# Power.net
KiCad netlist of a schematic drawn in Altium Designer
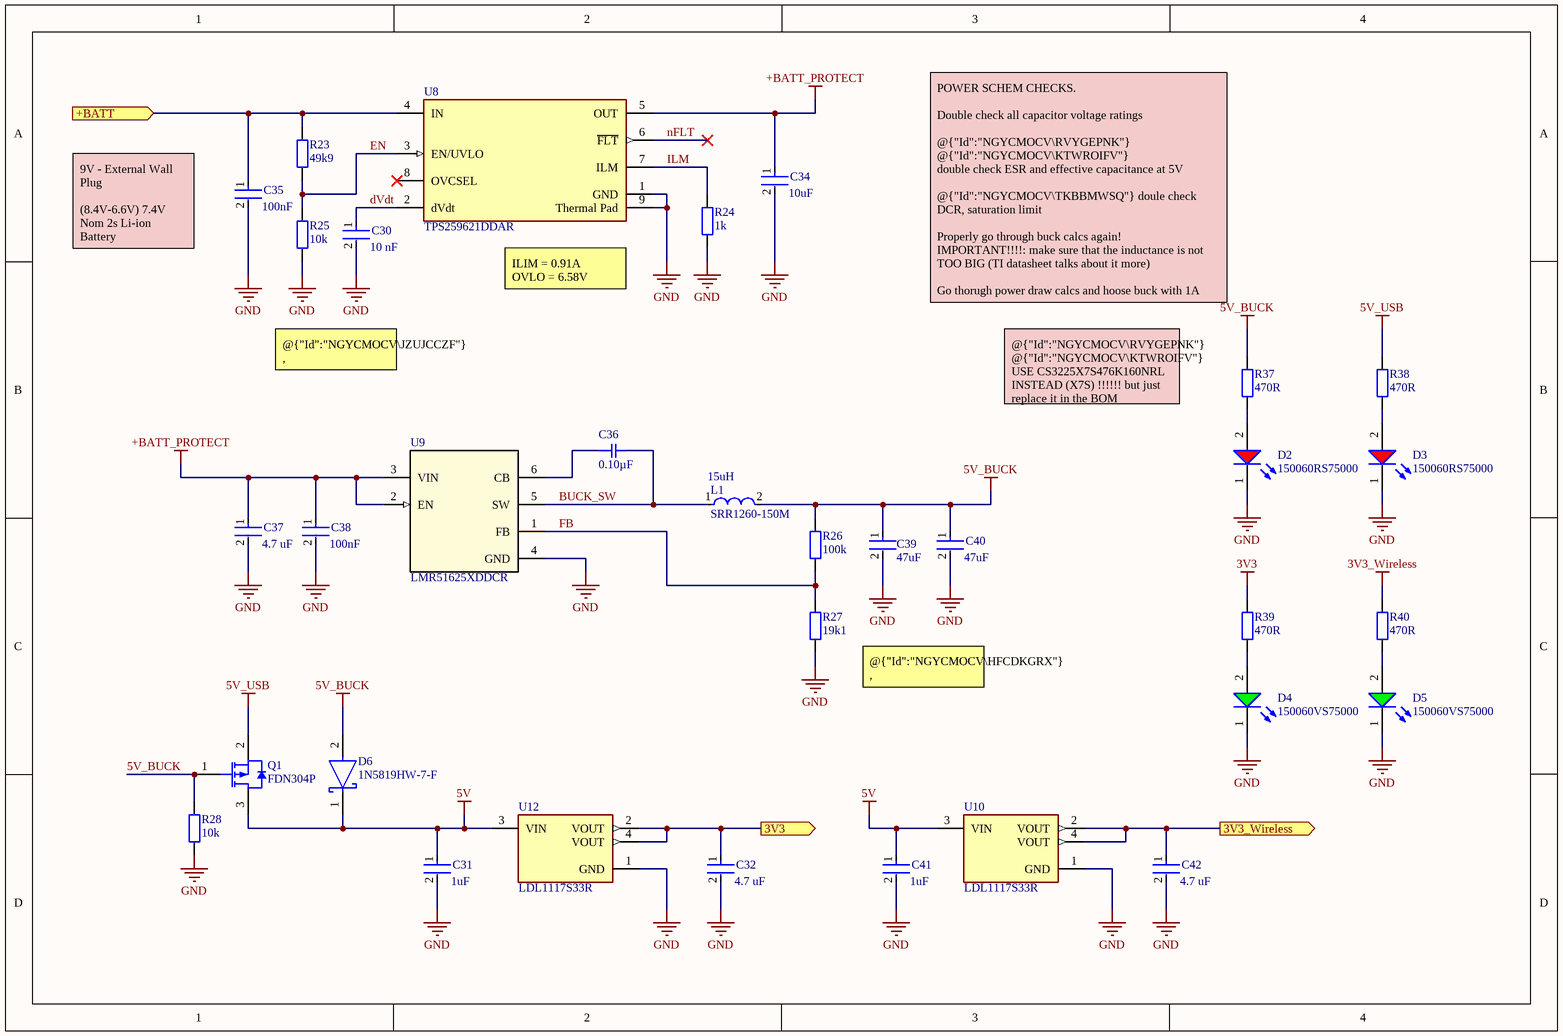
[diagram p0: Power.SchDoc]

(export (version "E")
  (design (tool "Eeschema 10.0.6"))
  (components
    (comp (ref "C30")
      (value "10 nF")
      (footprint "FP-CC0402-MFG")
      (description "CAP CER 10000PF 10V X7R 0402")
      (fields
        (field (name "MANUFACTURER") "YAGEO")
        (field (name "MANUFACTURER PART NUMBER") "CC0402KRX7R6BB103")
      )
      (libsource (lib "Altium Content Vault") (part "11868f565c42a9108669ba33697ecf6"))
    )
    (comp (ref "C31")
      (value "CL21B105KOFNNNE")
      (footprint "FP-CL21-IPC_A")
      (description "CL21 Series 0805 1uF 16V ±10% Tolerance X7R Multilayer Ceramic Chip Capacitor")
      (fields
        (field (name "CAPACITANCE") "1uF")
        (field (name "TOLERANCE") "10%")
        (field (name "VOLTAGE") "16V")
      )
      (libsource (lib "Altium Content Vault") (part "b4654b650e69147ec39a6b967a45e02"))
    )
    (comp (ref "C32")
      (value "4.7 uF")
      (footprint "FP-CC0805-0_85-MFG")
      (description "CAP CER 4.7UF 25V X7R 0805")
      (fields
        (field (name "OCTOPART") "https://octopart.com/cc0805kkx7r8bb475-yageo-51849247")
        (field (name "MANUFACTURER") "Yageo")
      )
      (libsource (lib "Altium Content Vault") (part "11868f565c42a9108669ba33697ecf6"))
    )
    (comp (ref "C34")
      (value "GRM21BC71E106KE11L")
      (footprint "FP-GRM21B-0_2-e0_2_0_7-MFG")
      (description "Chip Multilayer Ceramic Capacitors for General Purpose, 0805, 10uF, X7S, 22%, 10%, 25V")
      (fields
        (field (name "VOLTAGE") "25V")
        (field (name "CAPACITANCE") "10uF")
        (field (name "TOLERANCE") "10%")
      )
      (libsource (lib "Altium Content Vault") (part "b4654b650e69147ec39a6b967a45e02"))
    )
    (comp (ref "C35")
      (value "GRM155R61E104KA87D")
      (footprint "FP-GRM155-0_05-MFG")
      (description "CAP CER 0.1UF 25V X5R 0402")
      (fields
        (field (name "VOLTAGE") "25V")
        (field (name "CAPACITANCE") "100nF")
        (field (name "TOLERANCE") "10%")
      )
      (libsource (lib "Altium Content Vault") (part "11868f565c42a9108669ba33697ecf6"))
    )
    (comp (ref "C36")
      (value "0.10µF")
      (footprint "SMD-0402C")
      (description "CAP CER 0.1UF 10V X5R 0402")
      (fields (field (name "DIGI-KEY PART NUMBER") "490-6297-1-ND") (field (name "VOLTAGE") "10V"))
      (libsource (lib "University of British Columbia") (part "ZRB15XR61A475ME01D"))
    )
    (comp (ref "C37")
      (value "4.7 uF")
      (footprint "FP-CC0805-0_85-MFG")
      (description "CAP CER 4.7UF 25V X7R 0805")
      (fields
        (field (name "OCTOPART") "https://octopart.com/cc0805kkx7r8bb475-yageo-51849247")
        (field (name "MANUFACTURER") "Yageo")
      )
      (libsource (lib "Altium Content Vault") (part "11868f565c42a9108669ba33697ecf6"))
    )
    (comp (ref "C38")
      (value "GRM155R61E104KA87D")
      (footprint "FP-GRM155-0_05-MFG")
      (description "CAP CER 0.1UF 25V X5R 0402")
      (fields
        (field (name "VOLTAGE") "25V")
        (field (name "CAPACITANCE") "100nF")
        (field (name "TOLERANCE") "10%")
      )
      (libsource (lib "Altium Content Vault") (part "11868f565c42a9108669ba33697ecf6"))
    )
    (comp (ref "C39")
      (value "GRM32ER61C476KE15L")
      (footprint "FP-GRM32E-0_3-0_2-IPC_C")
      (description "CAP CER 47UF 16V X5R 1210")
      (fields
        (field (name "VOLTAGE") "16V")
        (field (name "TOLERANCE") "10%")
        (field (name "CAPACITANCE") "47uF")
      )
      (libsource (lib "Altium Content Vault") (part "b4654b650e69147ec39a6b967a45e02"))
    )
    (comp (ref "C40")
      (value "GRM32ER61C476KE15L")
      (footprint "FP-GRM32E-0_3-0_2-IPC_C")
      (description "CAP CER 47UF 16V X5R 1210")
      (fields
        (field (name "VOLTAGE") "16V")
        (field (name "TOLERANCE") "10%")
        (field (name "CAPACITANCE") "47uF")
      )
      (libsource (lib "Altium Content Vault") (part "b4654b650e69147ec39a6b967a45e02"))
    )
    (comp (ref "C41")
      (value "CL21B105KOFNNNE")
      (footprint "FP-CL21-IPC_A")
      (description "CL21 Series 0805 1uF 16V ±10% Tolerance X7R Multilayer Ceramic Chip Capacitor")
      (fields
        (field (name "CAPACITANCE") "1uF")
        (field (name "TOLERANCE") "10%")
        (field (name "VOLTAGE") "16V")
      )
      (libsource (lib "Altium Content Vault") (part "b4654b650e69147ec39a6b967a45e02"))
    )
    (comp (ref "C42")
      (value "4.7 uF")
      (footprint "FP-CC0805-0_85-MFG")
      (description "CAP CER 4.7UF 25V X7R 0805")
      (fields
        (field (name "OCTOPART") "https://octopart.com/cc0805kkx7r8bb475-yageo-51849247")
        (field (name "MANUFACTURER") "Yageo")
      )
      (libsource (lib "Altium Content Vault") (part "11868f565c42a9108669ba33697ecf6"))
    )
    (comp (ref "D2")
      (value "150060RS75000")
      (footprint "WL-SMCW_0603_150060xx75000")
      (description "LED Low-Power Uni-Color Red 630nm 2V 2-Pin Chip 0603(1608Metric) T/R")
      (libsource (lib "Altium Content Vault") (part "LED_Red_2A-1K"))
    )
    (comp (ref "D3")
      (value "150060RS75000")
      (footprint "WL-SMCW_0603_150060xx75000")
      (description "LED Low-Power Uni-Color Red 630nm 2V 2-Pin Chip 0603(1608Metric) T/R")
      (libsource (lib "Altium Content Vault") (part "LED_Red_2A-1K"))
    )
    (comp (ref "D4")
      (value "150060VS75000")
      (footprint "WL-SMCW_0603_150060xx75000")
      (description "WURTH ELEKTRONIK - 150060VS75000 - LED, Green, SMD, 0603, 30 mA, 2 V, 570 nm")
      (libsource (lib "Altium Content Vault") (part "LED_Green_2A-1K"))
    )
    (comp (ref "D5")
      (value "150060VS75000")
      (footprint "WL-SMCW_0603_150060xx75000")
      (description "WURTH ELEKTRONIK - 150060VS75000 - LED, Green, SMD, 0603, 30 mA, 2 V, 570 nm")
      (libsource (lib "Altium Content Vault") (part "LED_Green_2A-1K"))
    )
    (comp (ref "D6")
      (value "1N5819HW-7-F")
      (footprint "FP-SOD123-IPC_A")
      (description "DIODE SCHOTTKY 40V 1A SOD123")
      (libsource (lib "Altium Content Vault") (part "1d6ec82d83fb6aee721767c19dac4b9"))
    )
    (comp (ref "L1")
      (value "SRR1260-150M")
      (footprint "FP-SRR1260-MFG")
      (description "FIXED IND 15UH 5A 27 MOHM SMD")
      (fields (field (name "INDUCTANCE") "15uH") (field (name "TOLERANCE") "20%"))
      (libsource (lib "Altium Content Vault") (part "725321dda6339637d4d059423bc1c3c"))
    )
    (comp (ref "Q1")
      (value "FDN304P")
      (footprint "FAIR-SSOT3L-3_V")
      (fields (field (name "MANUFACTURER") "Fairchild Semiconductor"))
      (libsource (lib "Altium Content Vault") (part "PEMOS-GSD-3"))
    )
    (comp (ref "R23")
      (value "49k9")
      (footprint "IPC C R0402 NO SILK")
      (fields (field (name "Comment") "49.9k 1%"))
      (libsource (lib "Jack Kelly") (part "Generic RES 0603"))
    )
    (comp (ref "R24")
      (value "1k")
      (footprint "IPC C R0402 NO SILK")
      (fields (field (name "Comment") "1k 1%"))
      (libsource (lib "Jack Kelly") (part "Generic RES 0603"))
    )
    (comp (ref "R25")
      (value "10k")
      (footprint "IPC C R0402 NO SILK")
      (fields (field (name "Comment") "10k 1%"))
      (libsource (lib "Jack Kelly") (part "Generic RES 0603"))
    )
    (comp (ref "R26")
      (value "100k")
      (footprint "IPC C R0402 NO SILK")
      (fields (field (name "Comment") "100k 1%"))
      (libsource (lib "Jack Kelly") (part "Generic RES 0603"))
    )
    (comp (ref "R27")
      (value "19k1")
      (footprint "IPC C R0402 NO SILK")
      (fields (field (name "Comment") "19.1k 1%"))
      (libsource (lib "Jack Kelly") (part "Generic RES 0603"))
    )
    (comp (ref "R28")
      (value "10k")
      (footprint "IPC C R0402 NO SILK")
      (libsource (lib "Jack Kelly") (part "Generic RES 0603"))
    )
    (comp (ref "R37")
      (value "470R")
      (footprint "IPC C R0402 NO SILK")
      (libsource (lib "Jack Kelly") (part "Generic RES 0603"))
    )
    (comp (ref "R38")
      (value "470R")
      (footprint "IPC C R0402 NO SILK")
      (libsource (lib "Jack Kelly") (part "Generic RES 0603"))
    )
    (comp (ref "R39")
      (value "470R")
      (footprint "IPC C R0402 NO SILK")
      (libsource (lib "Jack Kelly") (part "Generic RES 0603"))
    )
    (comp (ref "R40")
      (value "470R")
      (footprint "IPC C R0402 NO SILK")
      (libsource (lib "Jack Kelly") (part "Generic RES 0603"))
    )
    (comp (ref "U8")
      (value "TPS259621DDAR")
      (footprint "FP-DDA0008J-IPC_A")
      (description "2.7-19V 130MA-2A SURGE CLAMPING")
      (libsource (lib "Altium Content Vault") (part "dcfcedcc3a9fb49b7817f2e200c0380"))
    )
    (comp (ref "U9")
      (value "LMR51625XDDCR")
      (footprint "DDC0006A-MFG")
      (fields (field (name "COPYRIGHT") "Copyright (C) 2025 Ultra Librarian. All rights reserved."))
      (libsource (lib "Jack Kelly") (part "LMR51625XDDCR"))
    )
    (comp (ref "U10")
      (value "LDL1117S33R")
      (footprint "FP-SOT223-0046067-IPC_C")
      (description "IC REG LINEAR 3.3V 1.2A SOT223")
      (fields
        (field (name "OCTOPART") "https://octopart.com/ldl1117s33r-stmicroelectronics-81876163")
        (field (name "MANUFACTURER") "STMicroelectronics")
      )
      (libsource (lib "Altium Content Vault") (part "a602d55cb6d43002de8a72f1c695f0a"))
    )
    (comp (ref "U12")
      (value "LDL1117S33R")
      (footprint "FP-SOT223-0046067-IPC_C")
      (description "IC REG LINEAR 3.3V 1.2A SOT223")
      (fields
        (field (name "OCTOPART") "https://octopart.com/ldl1117s33r-stmicroelectronics-81876163")
        (field (name "MANUFACTURER") "STMicroelectronics")
      )
      (libsource (lib "Altium Content Vault") (part "a602d55cb6d43002de8a72f1c695f0a"))
    )
  )
  (nets
    (net (code "1") (name "+BATT_PROTECT") (class "Default")
      (node (ref "C34") (pin "1") (pinfunction "1_1") (pintype "passive"))
      (node (ref "C37") (pin "1") (pinfunction "1_1") (pintype "passive"))
      (node (ref "C38") (pin "1") (pinfunction "1_1") (pintype "passive"))
      (node (ref "U8") (pin "5") (pinfunction "OUT_5") (pintype "passive"))
      (node (ref "U9") (pin "2") (pinfunction "EN_2") (pintype "input"))
      (node (ref "U9") (pin "3") (pinfunction "VIN_3") (pintype "power_in"))
    )
    (net (code "2") (name "/+BATT") (class "Default")
      (node (ref "C35") (pin "1") (pinfunction "1_1") (pintype "passive"))
      (node (ref "R23") (pin "2") (pinfunction "2_2") (pintype "passive"))
      (node (ref "U8") (pin "4") (pinfunction "IN_4") (pintype "power_in"))
    )
    (net (code "3") (name "/BUCK_SW") (class "Default")
      (node (ref "C36") (pin "2") (pinfunction "2_2") (pintype "passive"))
      (node (ref "L1") (pin "1") (pinfunction "1_1") (pintype "passive"))
      (node (ref "U9") (pin "5") (pinfunction "SW_5") (pintype "passive"))
    )
    (net (code "4") (name "/EN") (class "Default")
      (node (ref "R23") (pin "1") (pinfunction "1_1") (pintype "passive"))
      (node (ref "R25") (pin "2") (pinfunction "2_2") (pintype "passive"))
      (node (ref "U8") (pin "3") (pinfunction "EN/UVLO_3") (pintype "input"))
    )
    (net (code "5") (name "/FB") (class "Default")
      (node (ref "R26") (pin "1") (pinfunction "1_1") (pintype "passive"))
      (node (ref "R27") (pin "1") (pinfunction "1_1") (pintype "passive"))
      (node (ref "U9") (pin "1") (pinfunction "FB_1") (pintype "passive"))
    )
    (net (code "6") (name "/ILM") (class "Default")
      (node (ref "R24") (pin "2") (pinfunction "2_2") (pintype "passive"))
      (node (ref "U8") (pin "7") (pinfunction "ILM_7") (pintype "passive"))
    )
    (net (code "7") (name "/dVdt") (class "Default")
      (node (ref "C30") (pin "1") (pinfunction "1_1") (pintype "passive"))
      (node (ref "U8") (pin "2") (pinfunction "dVdt_2") (pintype "passive"))
    )
    (net (code "8") (name "/nFLT") (class "Default")
      (node (ref "U8") (pin "6") (pinfunction "~{FLT}_6") (pintype "output+no_connect"))
    )
    (net (code "9") (name "3V3") (class "Default")
      (node (ref "C32") (pin "1") (pinfunction "1_1") (pintype "passive"))
      (node (ref "R39") (pin "1") (pinfunction "1_1") (pintype "passive"))
      (node (ref "U12") (pin "2") (pinfunction "VOUT_2") (pintype "output"))
      (node (ref "U12") (pin "4") (pinfunction "VOUT_4") (pintype "output"))
    )
    (net (code "10") (name "3V3_Wireless") (class "Default")
      (node (ref "C42") (pin "1") (pinfunction "1_1") (pintype "passive"))
      (node (ref "R40") (pin "1") (pinfunction "1_1") (pintype "passive"))
      (node (ref "U10") (pin "2") (pinfunction "VOUT_2") (pintype "output"))
      (node (ref "U10") (pin "4") (pinfunction "VOUT_4") (pintype "output"))
    )
    (net (code "11") (name "5V") (class "Default")
      (node (ref "C31") (pin "1") (pinfunction "1_1") (pintype "passive"))
      (node (ref "C41") (pin "1") (pinfunction "1_1") (pintype "passive"))
      (node (ref "D6") (pin "1") (pinfunction "C_1") (pintype "passive"))
      (node (ref "Q1") (pin "3") (pinfunction "DRAIN_3") (pintype "passive"))
      (node (ref "U10") (pin "3") (pinfunction "VIN_3") (pintype "power_in"))
      (node (ref "U12") (pin "3") (pinfunction "VIN_3") (pintype "power_in"))
    )
    (net (code "12") (name "5V_BUCK") (class "Default")
      (node (ref "C39") (pin "1") (pinfunction "1_1") (pintype "passive"))
      (node (ref "C40") (pin "1") (pinfunction "1_1") (pintype "passive"))
      (node (ref "D6") (pin "2") (pinfunction "A_2") (pintype "passive"))
      (node (ref "L1") (pin "2") (pinfunction "2_2") (pintype "passive"))
      (node (ref "Q1") (pin "1") (pinfunction "GATE_1") (pintype "passive"))
      (node (ref "R26") (pin "2") (pinfunction "2_2") (pintype "passive"))
      (node (ref "R28") (pin "2") (pinfunction "2_2") (pintype "passive"))
      (node (ref "R37") (pin "1") (pinfunction "1_1") (pintype "passive"))
    )
    (net (code "13") (name "5V_USB") (class "Default")
      (node (ref "Q1") (pin "2") (pinfunction "SOURCE_2") (pintype "passive"))
      (node (ref "R38") (pin "1") (pinfunction "1_1") (pintype "passive"))
    )
    (net (code "14") (name "GND") (class "Default")
      (node (ref "C30") (pin "2") (pinfunction "2_2") (pintype "passive"))
      (node (ref "C31") (pin "2") (pinfunction "2_2") (pintype "passive"))
      (node (ref "C32") (pin "2") (pinfunction "2_2") (pintype "passive"))
      (node (ref "C34") (pin "2") (pinfunction "2_2") (pintype "passive"))
      (node (ref "C35") (pin "2") (pinfunction "2_2") (pintype "passive"))
      (node (ref "C37") (pin "2") (pinfunction "2_2") (pintype "passive"))
      (node (ref "C38") (pin "2") (pinfunction "2_2") (pintype "passive"))
      (node (ref "C39") (pin "2") (pinfunction "2_2") (pintype "passive"))
      (node (ref "C40") (pin "2") (pinfunction "2_2") (pintype "passive"))
      (node (ref "C41") (pin "2") (pinfunction "2_2") (pintype "passive"))
      (node (ref "C42") (pin "2") (pinfunction "2_2") (pintype "passive"))
      (node (ref "D2") (pin "1") (pinfunction "K_1") (pintype "passive"))
      (node (ref "D3") (pin "1") (pinfunction "K_1") (pintype "passive"))
      (node (ref "D4") (pin "1") (pinfunction "K_1") (pintype "passive"))
      (node (ref "D5") (pin "1") (pinfunction "K_1") (pintype "passive"))
      (node (ref "R24") (pin "1") (pinfunction "1_1") (pintype "passive"))
      (node (ref "R25") (pin "1") (pinfunction "1_1") (pintype "passive"))
      (node (ref "R27") (pin "2") (pinfunction "2_2") (pintype "passive"))
      (node (ref "R28") (pin "1") (pinfunction "1_1") (pintype "passive"))
      (node (ref "U10") (pin "1") (pinfunction "GND_1") (pintype "power_in"))
      (node (ref "U12") (pin "1") (pinfunction "GND_1") (pintype "power_in"))
      (node (ref "U8") (pin "1") (pinfunction "GND_1") (pintype "power_in"))
      (node (ref "U8") (pin "9") (pinfunction "Thermal_Pad_9") (pintype "passive"))
      (node (ref "U9") (pin "4") (pinfunction "GND_4") (pintype "power_in"))
    )
    (net (code "15") (name "Net-(D2-A)") (class "Default")
      (node (ref "D2") (pin "2") (pinfunction "A_2") (pintype "passive"))
      (node (ref "R37") (pin "2") (pinfunction "2_2") (pintype "passive"))
    )
    (net (code "16") (name "Net-(D3-A)") (class "Default")
      (node (ref "D3") (pin "2") (pinfunction "A_2") (pintype "passive"))
      (node (ref "R38") (pin "2") (pinfunction "2_2") (pintype "passive"))
    )
    (net (code "17") (name "Net-(D4-A)") (class "Default")
      (node (ref "D4") (pin "2") (pinfunction "A_2") (pintype "passive"))
      (node (ref "R39") (pin "2") (pinfunction "2_2") (pintype "passive"))
    )
    (net (code "18") (name "Net-(D5-A)") (class "Default")
      (node (ref "D5") (pin "2") (pinfunction "A_2") (pintype "passive"))
      (node (ref "R40") (pin "2") (pinfunction "2_2") (pintype "passive"))
    )
    (net (code "19") (name "Net-(U9-CB)") (class "Default")
      (node (ref "C36") (pin "1") (pinfunction "1_1") (pintype "passive"))
      (node (ref "U9") (pin "6") (pinfunction "CB_6") (pintype "passive"))
    )
    (net (code "20") (name "unconnected-(U8-OVCSEL-Pad8)") (class "Default")
      (node (ref "U8") (pin "8") (pinfunction "OVCSEL_8") (pintype "passive+no_connect"))
    )
  )
)
